# Top_Level.net
KiCad netlist of a schematic drawn in Altium Designer
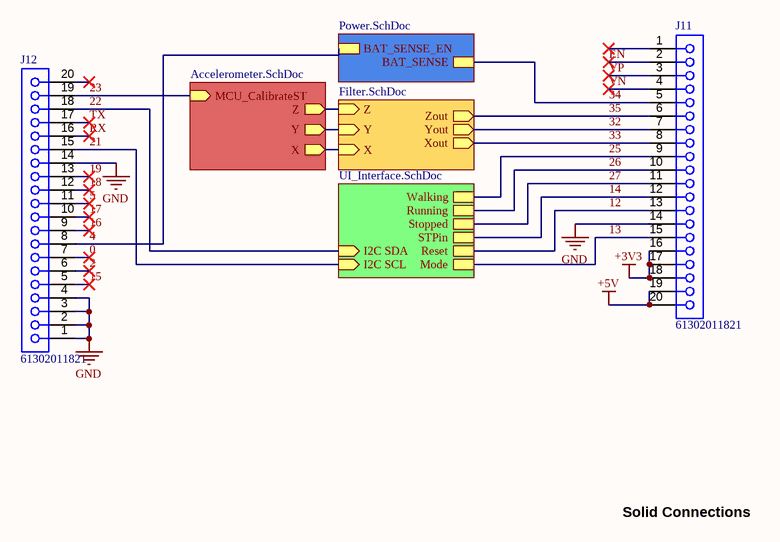
[diagram p0: Top Level.SchDoc]

(export (version "E")
  (design (tool "Eeschema 10.0.6"))
  (components
    (comp (ref "J11")
      (value "61302011821")
      (footprint "61302011821")
      (libsource (lib "Altium Content Vault") (part "Header_Female_1R_20P"))
    )
    (comp (ref "J12")
      (value "61302011821")
      (footprint "61302011821")
      (libsource (lib "Altium Content Vault") (part "Header_Female_1R_20P"))
    )
  )
  (nets
    (net (code "1") (name "+3V3") (class "Default")
      (node (ref "J11") (pin "16") (pinfunction "16_16") (pintype "passive"))
      (node (ref "J11") (pin "17") (pinfunction "17_17") (pintype "passive"))
      (node (ref "J11") (pin "18") (pinfunction "18_18") (pintype "passive"))
    )
    (net (code "2") (name "+5V") (class "Default")
      (node (ref "J11") (pin "19") (pinfunction "19_19") (pintype "passive"))
      (node (ref "J11") (pin "20") (pinfunction "20_20") (pintype "passive"))
    )
    (net (code "3") (name "/0") (class "Default")
      (node (ref "J12") (pin "7") (pinfunction "7_7") (pintype "passive+no_connect"))
    )
    (net (code "4") (name "/2") (class "Default")
      (node (ref "J12") (pin "6") (pinfunction "6_6") (pintype "passive+no_connect"))
    )
    (net (code "5") (name "/4") (class "Default")
      (node (ref "J12") (pin "8") (pinfunction "8_8") (pintype "passive"))
    )
    (net (code "6") (name "/5") (class "Default")
      (node (ref "J12") (pin "11") (pinfunction "11_11") (pintype "passive+no_connect"))
    )
    (net (code "7") (name "/12") (class "Default")
      (node (ref "J11") (pin "13") (pinfunction "13_13") (pintype "passive"))
    )
    (net (code "8") (name "/13") (class "Default")
      (node (ref "J11") (pin "15") (pinfunction "15_15") (pintype "passive"))
    )
    (net (code "9") (name "/14") (class "Default")
      (node (ref "J11") (pin "12") (pinfunction "12_12") (pintype "passive"))
    )
    (net (code "10") (name "/15") (class "Default")
      (node (ref "J12") (pin "5") (pinfunction "5_5") (pintype "passive+no_connect"))
    )
    (net (code "11") (name "/16") (class "Default")
      (node (ref "J12") (pin "9") (pinfunction "9_9") (pintype "passive+no_connect"))
    )
    (net (code "12") (name "/17") (class "Default")
      (node (ref "J12") (pin "10") (pinfunction "10_10") (pintype "passive+no_connect"))
    )
    (net (code "13") (name "/18") (class "Default")
      (node (ref "J12") (pin "12") (pinfunction "12_12") (pintype "passive+no_connect"))
    )
    (net (code "14") (name "/19") (class "Default")
      (node (ref "J12") (pin "13") (pinfunction "13_13") (pintype "passive+no_connect"))
    )
    (net (code "15") (name "/21") (class "Default")
      (node (ref "J12") (pin "15") (pinfunction "15_15") (pintype "passive"))
    )
    (net (code "16") (name "/22") (class "Default")
      (node (ref "J12") (pin "18") (pinfunction "18_18") (pintype "passive"))
    )
    (net (code "17") (name "/23") (class "Default")
      (node (ref "J12") (pin "19") (pinfunction "19_19") (pintype "passive"))
    )
    (net (code "18") (name "/25") (class "Default")
      (node (ref "J11") (pin "9") (pinfunction "9_9") (pintype "passive"))
    )
    (net (code "19") (name "/26") (class "Default")
      (node (ref "J11") (pin "10") (pinfunction "10_10") (pintype "passive"))
    )
    (net (code "20") (name "/27") (class "Default")
      (node (ref "J11") (pin "11") (pinfunction "11_11") (pintype "passive"))
    )
    (net (code "21") (name "/32") (class "Default")
      (node (ref "J11") (pin "7") (pinfunction "7_7") (pintype "passive"))
    )
    (net (code "22") (name "/33") (class "Default")
      (node (ref "J11") (pin "8") (pinfunction "8_8") (pintype "passive"))
    )
    (net (code "23") (name "/34") (class "Default")
      (node (ref "J11") (pin "5") (pinfunction "5_5") (pintype "passive"))
    )
    (net (code "24") (name "/35") (class "Default")
      (node (ref "J11") (pin "6") (pinfunction "6_6") (pintype "passive"))
    )
    (net (code "25") (name "/EN") (class "Default")
      (node (ref "J11") (pin "2") (pinfunction "2_2") (pintype "passive+no_connect"))
    )
    (net (code "26") (name "/RX") (class "Default")
      (node (ref "J12") (pin "16") (pinfunction "16_16") (pintype "passive+no_connect"))
    )
    (net (code "27") (name "/TX") (class "Default")
      (node (ref "J12") (pin "17") (pinfunction "17_17") (pintype "passive+no_connect"))
    )
    (net (code "28") (name "/VN") (class "Default")
      (node (ref "J11") (pin "4") (pinfunction "4_4") (pintype "passive+no_connect"))
    )
    (net (code "29") (name "/VP") (class "Default")
      (node (ref "J11") (pin "3") (pinfunction "3_3") (pintype "passive+no_connect"))
    )
    (net (code "33") (name "GND") (class "Default")
      (node (ref "J11") (pin "14") (pinfunction "14_14") (pintype "passive"))
      (node (ref "J12") (pin "1") (pinfunction "1_1") (pintype "passive"))
      (node (ref "J12") (pin "14") (pinfunction "14_14") (pintype "passive"))
      (node (ref "J12") (pin "2") (pinfunction "2_2") (pintype "passive"))
      (node (ref "J12") (pin "3") (pinfunction "3_3") (pintype "passive"))
      (node (ref "J12") (pin "4") (pinfunction "4_4") (pintype "passive"))
    )
    (net (code "34") (name "unconnected-(J11-Pad1)") (class "Default")
      (node (ref "J11") (pin "1") (pinfunction "1_1") (pintype "passive+no_connect"))
    )
    (net (code "35") (name "unconnected-(J12-Pad20)") (class "Default")
      (node (ref "J12") (pin "20") (pinfunction "20_20") (pintype "passive+no_connect"))
    )
  )
)
